# InWall_Schem2.net
KiCad netlist of a schematic drawn in Altium Designer
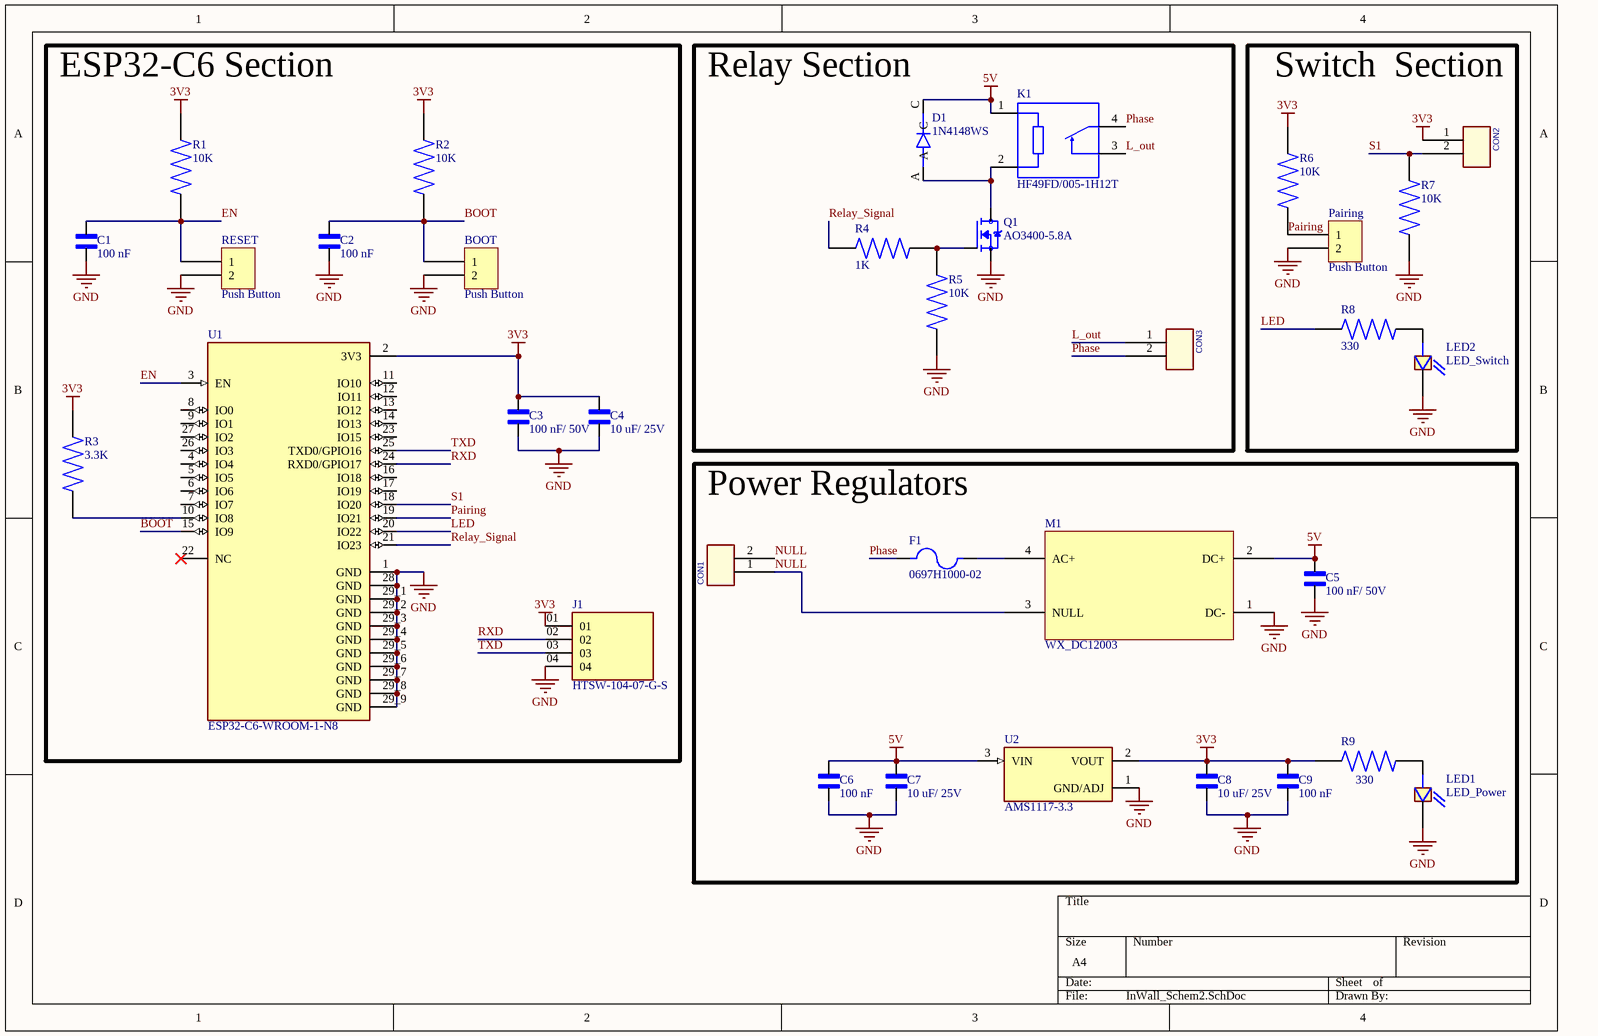
[diagram p0: InWall_Schem2.SchDoc]

(export (version "E")
  (design (tool "Eeschema 10.0.6"))
  (components
    (comp (ref "BOOT")
      (value "Push Button")
      (footprint "Push Button")
      (libsource (lib "zigbee_orangepi") (part "Push Button"))
    )
    (comp (ref "C1")
      (value "100 nF")
      (footprint "CAPC2012X90N")
      (description "Capacitor: ceramic; MLCC; 100nF; 25V; X7R; Â±10%; SMD; 0805")
      (fields (field (name "MF") "Vishay Vitramon") (field (name "MP") "VJ0805Y104KXXCW1BC"))
      (libsource (lib "Smart_InWall") (part "VJ0805Y104KXXCW1BC"))
    )
    (comp (ref "C2")
      (value "100 nF")
      (footprint "CAPC2012X90N")
      (description "Capacitor: ceramic; MLCC; 100nF; 25V; X7R; Â±10%; SMD; 0805")
      (fields (field (name "MF") "Vishay Vitramon") (field (name "MP") "VJ0805Y104KXXCW1BC"))
      (libsource (lib "Smart_InWall") (part "VJ0805Y104KXXCW1BC"))
    )
    (comp (ref "C3")
      (value "100 nF/ 50V")
      (footprint "CAPC2012X90N")
      (description "Capacitor: ceramic; MLCC; 100nF; 25V; X7R; Â±10%; SMD; 0805")
      (fields (field (name "MF") "Vishay Vitramon") (field (name "MP") "VJ0805Y104KXXCW1BC"))
      (libsource (lib "Smart_InWall") (part "VJ0805Y104KXXCW1BC"))
    )
    (comp (ref "C4")
      (value "10 uF/ 25V")
      (footprint "CAPC2012X90N")
      (description "Capacitor: ceramic; MLCC; 100nF; 25V; X7R; Â±10%; SMD; 0805")
      (fields (field (name "MF") "Vishay Vitramon") (field (name "MP") "VJ0805Y104KXXCW1BC"))
      (libsource (lib "Smart_InWall") (part "VJ0805Y104KXXCW1BC"))
    )
    (comp (ref "C5")
      (value "100 nF/ 50V")
      (footprint "CAPC2012X90N")
      (description "Capacitor: ceramic; MLCC; 100nF; 25V; X7R; Â±10%; SMD; 0805")
      (fields (field (name "MF") "Vishay Vitramon") (field (name "MP") "VJ0805Y104KXXCW1BC"))
      (libsource (lib "Smart_InWall") (part "VJ0805Y104KXXCW1BC"))
    )
    (comp (ref "C6")
      (value "100 nF")
      (footprint "CAPC2012X90N")
      (description "Capacitor: ceramic; MLCC; 100nF; 25V; X7R; Â±10%; SMD; 0805")
      (fields (field (name "MF") "Vishay Vitramon") (field (name "MP") "VJ0805Y104KXXCW1BC"))
      (libsource (lib "Smart_InWall") (part "VJ0805Y104KXXCW1BC"))
    )
    (comp (ref "C7")
      (value "10 uF/ 25V")
      (footprint "CAPC2012X90N")
      (description "Capacitor: ceramic; MLCC; 100nF; 25V; X7R; Â±10%; SMD; 0805")
      (fields (field (name "MF") "Vishay Vitramon") (field (name "MP") "VJ0805Y104KXXCW1BC"))
      (libsource (lib "Smart_InWall") (part "VJ0805Y104KXXCW1BC"))
    )
    (comp (ref "C8")
      (value "10 uF/ 25V")
      (footprint "CAPC2012X90N")
      (description "Capacitor: ceramic; MLCC; 100nF; 25V; X7R; Â±10%; SMD; 0805")
      (fields (field (name "MF") "Vishay Vitramon") (field (name "MP") "VJ0805Y104KXXCW1BC"))
      (libsource (lib "Smart_InWall") (part "VJ0805Y104KXXCW1BC"))
    )
    (comp (ref "C9")
      (value "100 nF")
      (footprint "CAPC2012X90N")
      (description "Capacitor: ceramic; MLCC; 100nF; 25V; X7R; Â±10%; SMD; 0805")
      (fields (field (name "MF") "Vishay Vitramon") (field (name "MP") "VJ0805Y104KXXCW1BC"))
      (libsource (lib "Smart_InWall") (part "VJ0805Y104KXXCW1BC"))
    )
    (comp (ref "CON1") (value "CON2") (footprint "TB_2") (libsource (lib "") (part "CON2_1")))
    (comp (ref "CON2") (value "CON2") (footprint "TB_2") (libsource (lib "Smart_InWall") (part "CON2")))
    (comp (ref "CON3") (value "CON2") (footprint "TB_2") (libsource (lib "Smart_InWall") (part "CON2")))
    (comp (ref "D1")
      (value "1N4148WS")
      (footprint "SODFL2512X100N")
      (description "Diode Standard 75V 300mA (DC) Surface Mount SOD-323")
      (fields (field (name "MF") "ON Semiconductor"))
      (libsource (lib "smartplug") (part "1N4148WS"))
    )
    (comp (ref "F1")
      (value "0697H1000-02")
      (footprint "FUSRR508W60L835T400H810")
      (description "2-Pin Radial Fuse ¦ Rectangular ¦ Slow Blow ¦ UL ¦ Ammo Pack ¦ 1A")
      (fields (field (name "MF") "Bel Fuse"))
      (libsource (lib "Smart_InWall") (part "0697H1000-02"))
    )
    (comp (ref "J1")
      (value "HTSW-104-07-G-S")
      (footprint "SAMTEC_HTSW-104-07-G-S")
      (libsource (lib "ZigbeeHub") (part "HTSW-104-07-G-S"))
    )
    (comp (ref "K1")
      (value "HF49FD/005-1H12T")
      (footprint "RELAY_HF49FD/005-1H12T")
      (description "Relay: electromagnetic; SPST-NO; Ucoil: 5VDC; 5A/250VAC; 5A/30VDC")
      (fields (field (name "MF") "Hongfa"))
      (libsource (lib "Smart_InWall") (part "HF49FD/005-1H12T"))
    )
    (comp (ref "LED1")
      (value "LED_Power")
      (footprint "LEDRD254W50D305H520P")
      (description "Ovlaw4Cb7 White LED 3mm (T-1) Round Lens Through Hole Package ¦ Optek (TT Electronics) OVLAW4CB7")
      (fields (field (name "MF") "TT Electronics/Optek") (field (name "MP") "OVLAW4CB7"))
      (libsource (lib "ZigbeeHub") (part "OVLAW4CB7"))
    )
    (comp (ref "LED2")
      (value "LED_Switch")
      (footprint "LEDRD254W50D305H520P")
      (description "Ovlaw4Cb7 White LED 3mm (T-1) Round Lens Through Hole Package ¦ Optek (TT Electronics) OVLAW4CB7")
      (fields (field (name "MF") "TT Electronics/Optek") (field (name "MP") "OVLAW4CB7"))
      (libsource (lib "ZigbeeHub") (part "OVLAW4CB7"))
    )
    (comp (ref "M1")
      (value "WX_DC12003")
      (footprint "WX-DC12003")
      (libsource (lib "Smart_InWall") (part "WX_DC12003"))
    )
    (comp (ref "Pairing")
      (value "Push Button")
      (footprint "Push Button")
      (libsource (lib "zigbee_orangepi") (part "Push Button"))
    )
    (comp (ref "Q1")
      (value "AO3400-5.8A")
      (footprint "SOT95P260X140-3N")
      (fields (field (name "MF") "{'manufacturer': u'MDD'}"))
      (libsource (lib "Smart_InWall") (part "AO3400-5.8A"))
    )
    (comp (ref "R1")
      (value "10K")
      (footprint "RESC2012X65N")
      (description "RES SMD 5.11KOHM 0.1% 1/10W 0805")
      (fields (field (name "MF") "TE Connectivity") (field (name "MP") "RN73C2A5K11BTD"))
      (libsource (lib "Smart_InWall") (part "RN73C2A5K11BTD"))
    )
    (comp (ref "R2")
      (value "10K")
      (footprint "RESC2012X65N")
      (description "RES SMD 5.11KOHM 0.1% 1/10W 0805")
      (fields (field (name "MF") "TE Connectivity") (field (name "MP") "RN73C2A5K11BTD"))
      (libsource (lib "Smart_InWall") (part "RN73C2A5K11BTD"))
    )
    (comp (ref "R3")
      (value "3.3K")
      (footprint "RESC2012X65N")
      (description "RES SMD 5.11KOHM 0.1% 1/10W 0805")
      (fields (field (name "MF") "TE Connectivity") (field (name "MP") "RN73C2A5K11BTD"))
      (libsource (lib "Smart_InWall") (part "RN73C2A5K11BTD"))
    )
    (comp (ref "R4")
      (value "1K")
      (footprint "RESC2012X65N")
      (description "RES SMD 5.11KOHM 0.1% 1/10W 0805")
      (fields (field (name "MF") "TE Connectivity") (field (name "MP") "RN73C2A5K11BTD"))
      (libsource (lib "Smart_InWall") (part "RN73C2A5K11BTD"))
    )
    (comp (ref "R5")
      (value "10K")
      (footprint "RESC2012X65N")
      (description "RES SMD 5.11KOHM 0.1% 1/10W 0805")
      (fields (field (name "MF") "TE Connectivity") (field (name "MP") "RN73C2A5K11BTD"))
      (libsource (lib "Smart_InWall") (part "RN73C2A5K11BTD"))
    )
    (comp (ref "R6")
      (value "10K")
      (footprint "RESC2012X65N")
      (description "RES SMD 5.11KOHM 0.1% 1/10W 0805")
      (fields (field (name "MF") "TE Connectivity") (field (name "MP") "RN73C2A5K11BTD"))
      (libsource (lib "Smart_InWall") (part "RN73C2A5K11BTD"))
    )
    (comp (ref "R7")
      (value "10K")
      (footprint "RESC2012X65N")
      (description "RES SMD 5.11KOHM 0.1% 1/10W 0805")
      (fields (field (name "MF") "TE Connectivity") (field (name "MP") "RN73C2A5K11BTD"))
      (libsource (lib "Smart_InWall") (part "RN73C2A5K11BTD"))
    )
    (comp (ref "R8")
      (value "330")
      (footprint "RESC2012X65N")
      (description "RES SMD 5.11KOHM 0.1% 1/10W 0805")
      (fields (field (name "MF") "TE Connectivity") (field (name "MP") "RN73C2A5K11BTD"))
      (libsource (lib "Smart_InWall") (part "RN73C2A5K11BTD"))
    )
    (comp (ref "R9")
      (value "330")
      (footprint "RESC2012X65N")
      (description "RES SMD 5.11KOHM 0.1% 1/10W 0805")
      (fields (field (name "MF") "TE Connectivity") (field (name "MP") "RN73C2A5K11BTD"))
      (libsource (lib "Smart_InWall") (part "RN73C2A5K11BTD"))
    )
    (comp (ref "RESET")
      (value "Push Button")
      (footprint "Push Button")
      (libsource (lib "zigbee_orangepi") (part "Push Button"))
    )
    (comp (ref "U1")
      (value "ESP32-C6-WROOM-1-N8")
      (footprint "XCVR_ESP32-C6-WROOM-1-N8")
      (fields (field (name "MF") "Espressif Systems"))
      (libsource (lib "Smart_InWall") (part "ESP32-C6-WROOM-1-N8"))
    )
    (comp (ref "U2")
      (value "AMS1117-3.3")
      (footprint "SOT229P700X180-4N")
      (description "Sot223/Pkg 1-Amp 3.3-Volt Low Drop Out Voltage Regulatator")
      (fields (field (name "MF") "Advanced Monolithic Systems"))
      (libsource (lib "ZigbeeHub") (part "AMS1117-3.3"))
    )
  )
  (nets
    (net (code "1") (name "/BOOT") (class "Default")
      (node (ref "BOOT") (pin "1") (pinfunction "1_1") (pintype "passive"))
      (node (ref "C2") (pin "2") (pinfunction "2_2") (pintype "passive"))
      (node (ref "R2") (pin "2") (pinfunction "2_2") (pintype "passive"))
      (node (ref "U1") (pin "15") (pinfunction "IO9_15") (pintype "bidirectional"))
    )
    (net (code "2") (name "/EN") (class "Default")
      (node (ref "C1") (pin "2") (pinfunction "2_2") (pintype "passive"))
      (node (ref "R1") (pin "2") (pinfunction "2_2") (pintype "passive"))
      (node (ref "RESET") (pin "1") (pinfunction "1_1") (pintype "passive"))
      (node (ref "U1") (pin "3") (pinfunction "EN_3") (pintype "input"))
    )
    (net (code "3") (name "/LED") (class "Default")
      (node (ref "R8") (pin "1") (pinfunction "1_1") (pintype "passive"))
      (node (ref "U1") (pin "20") (pinfunction "IO22_20") (pintype "bidirectional"))
    )
    (net (code "4") (name "/L_out") (class "Default")
      (node (ref "CON3") (pin "1") (pinfunction "1_1") (pintype "passive"))
      (node (ref "K1") (pin "3") (pinfunction "C2_3") (pintype "passive"))
    )
    (net (code "5") (name "/NULL") (class "Default")
      (node (ref "CON1") (pin "1") (pinfunction "1_1") (pintype "passive"))
      (node (ref "CON1") (pin "2") (pinfunction "2_2") (pintype "passive"))
      (node (ref "M1") (pin "3") (pinfunction "NULL_3") (pintype "passive"))
    )
    (net (code "6") (name "/Pairing") (class "Default")
      (node (ref "Pairing") (pin "1") (pinfunction "1_1") (pintype "passive"))
      (node (ref "R6") (pin "2") (pinfunction "2_2") (pintype "passive"))
      (node (ref "U1") (pin "19") (pinfunction "IO21_19") (pintype "bidirectional"))
    )
    (net (code "7") (name "/Phase") (class "Default")
      (node (ref "CON3") (pin "2") (pinfunction "2_2") (pintype "passive"))
      (node (ref "F1") (pin "1") (pinfunction "1_1") (pintype "passive"))
      (node (ref "K1") (pin "4") (pinfunction "C1_4") (pintype "passive"))
    )
    (net (code "8") (name "/RXD") (class "Default")
      (node (ref "J1") (pin "02") (pinfunction "02_02") (pintype "passive"))
      (node (ref "U1") (pin "24") (pinfunction "RXD0/GPIO17_24") (pintype "bidirectional"))
    )
    (net (code "9") (name "/Relay_Signal") (class "Default")
      (node (ref "R4") (pin "1") (pinfunction "1_1") (pintype "passive"))
      (node (ref "U1") (pin "21") (pinfunction "IO23_21") (pintype "bidirectional"))
    )
    (net (code "10") (name "/S1") (class "Default")
      (node (ref "CON2") (pin "2") (pinfunction "2_2") (pintype "passive"))
      (node (ref "R7") (pin "1") (pinfunction "1_1") (pintype "passive"))
      (node (ref "U1") (pin "18") (pinfunction "IO20_18") (pintype "bidirectional"))
    )
    (net (code "11") (name "/TXD") (class "Default")
      (node (ref "J1") (pin "03") (pinfunction "03_03") (pintype "passive"))
      (node (ref "U1") (pin "25") (pinfunction "TXD0/GPIO16_25") (pintype "bidirectional"))
    )
    (net (code "12") (name "3V3") (class "Default")
      (node (ref "C3") (pin "2") (pinfunction "2_2") (pintype "passive"))
      (node (ref "C4") (pin "2") (pinfunction "2_2") (pintype "passive"))
      (node (ref "C8") (pin "2") (pinfunction "2_2") (pintype "passive"))
      (node (ref "C9") (pin "2") (pinfunction "2_2") (pintype "passive"))
      (node (ref "CON2") (pin "1") (pinfunction "1_1") (pintype "passive"))
      (node (ref "J1") (pin "01") (pinfunction "01_01") (pintype "passive"))
      (node (ref "R1") (pin "1") (pinfunction "1_1") (pintype "passive"))
      (node (ref "R2") (pin "1") (pinfunction "1_1") (pintype "passive"))
      (node (ref "R3") (pin "2") (pinfunction "2_2") (pintype "passive"))
      (node (ref "R6") (pin "1") (pinfunction "1_1") (pintype "passive"))
      (node (ref "R9") (pin "1") (pinfunction "1_1") (pintype "passive"))
      (node (ref "U1") (pin "2") (pinfunction "3V3_2") (pintype "power_in"))
      (node (ref "U2") (pin "2") (pinfunction "VOUT_2") (pintype "power_in"))
    )
    (net (code "13") (name "5V") (class "Default")
      (node (ref "C5") (pin "2") (pinfunction "2_2") (pintype "passive"))
      (node (ref "C6") (pin "2") (pinfunction "2_2") (pintype "passive"))
      (node (ref "C7") (pin "2") (pinfunction "2_2") (pintype "passive"))
      (node (ref "D1") (pin "C") (pinfunction "C_C") (pintype "passive"))
      (node (ref "K1") (pin "1") (pinfunction "L1_1") (pintype "passive"))
      (node (ref "M1") (pin "2") (pinfunction "DC+_2") (pintype "passive"))
      (node (ref "U2") (pin "3") (pinfunction "VIN_3") (pintype "input"))
    )
    (net (code "14") (name "GND") (class "Default")
      (node (ref "BOOT") (pin "2") (pinfunction "2_2") (pintype "passive"))
      (node (ref "C1") (pin "1") (pinfunction "1_1") (pintype "passive"))
      (node (ref "C2") (pin "1") (pinfunction "1_1") (pintype "passive"))
      (node (ref "C3") (pin "1") (pinfunction "1_1") (pintype "passive"))
      (node (ref "C4") (pin "1") (pinfunction "1_1") (pintype "passive"))
      (node (ref "C5") (pin "1") (pinfunction "1_1") (pintype "passive"))
      (node (ref "C6") (pin "1") (pinfunction "1_1") (pintype "passive"))
      (node (ref "C7") (pin "1") (pinfunction "1_1") (pintype "passive"))
      (node (ref "C8") (pin "1") (pinfunction "1_1") (pintype "passive"))
      (node (ref "C9") (pin "1") (pinfunction "1_1") (pintype "passive"))
      (node (ref "J1") (pin "04") (pinfunction "04_04") (pintype "passive"))
      (node (ref "LED1") (pin "C") (pinfunction "C_C") (pintype "passive"))
      (node (ref "LED2") (pin "C") (pinfunction "C_C") (pintype "passive"))
      (node (ref "M1") (pin "1") (pinfunction "DC-_1") (pintype "passive"))
      (node (ref "Pairing") (pin "2") (pinfunction "2_2") (pintype "passive"))
      (node (ref "Q1") (pin "2") (pinfunction "S_2") (pintype "passive"))
      (node (ref "R5") (pin "1") (pinfunction "1_1") (pintype "passive"))
      (node (ref "R7") (pin "2") (pinfunction "2_2") (pintype "passive"))
      (node (ref "RESET") (pin "2") (pinfunction "2_2") (pintype "passive"))
      (node (ref "U1") (pin "1") (pinfunction "GND_1") (pintype "power_in"))
      (node (ref "U1") (pin "28") (pinfunction "GND_28") (pintype "power_in"))
      (node (ref "U1") (pin "29_1") (pinfunction "GND_29_1") (pintype "power_in"))
      (node (ref "U1") (pin "29_2") (pinfunction "GND_29_2") (pintype "power_in"))
      (node (ref "U1") (pin "29_3") (pinfunction "GND_29_3") (pintype "power_in"))
      (node (ref "U1") (pin "29_4") (pinfunction "GND_29_4") (pintype "power_in"))
      (node (ref "U1") (pin "29_5") (pinfunction "GND_29_5") (pintype "power_in"))
      (node (ref "U1") (pin "29_6") (pinfunction "GND_29_6") (pintype "power_in"))
      (node (ref "U1") (pin "29_7") (pinfunction "GND_29_7") (pintype "power_in"))
      (node (ref "U1") (pin "29_8") (pinfunction "GND_29_8") (pintype "power_in"))
      (node (ref "U1") (pin "29_9") (pinfunction "GND_29_9") (pintype "power_in"))
      (node (ref "U2") (pin "1") (pinfunction "GND/ADJ_1") (pintype "power_in"))
    )
    (net (code "15") (name "Net-(K1-L2)") (class "Default")
      (node (ref "D1") (pin "A") (pinfunction "A_A") (pintype "passive"))
      (node (ref "K1") (pin "2") (pinfunction "L2_2") (pintype "passive"))
      (node (ref "Q1") (pin "3") (pinfunction "D_3") (pintype "passive"))
    )
    (net (code "16") (name "Net-(LED1-PadA)") (class "Default")
      (node (ref "LED1") (pin "A") (pinfunction "A_A") (pintype "passive"))
      (node (ref "R9") (pin "2") (pinfunction "2_2") (pintype "passive"))
    )
    (net (code "17") (name "Net-(LED2-PadA)") (class "Default")
      (node (ref "LED2") (pin "A") (pinfunction "A_A") (pintype "passive"))
      (node (ref "R8") (pin "2") (pinfunction "2_2") (pintype "passive"))
    )
    (net (code "18") (name "Net-(M1-AC+)") (class "Default")
      (node (ref "F1") (pin "2") (pinfunction "2_2") (pintype "passive"))
      (node (ref "M1") (pin "4") (pinfunction "AC+_4") (pintype "passive"))
    )
    (net (code "19") (name "Net-(Q1-G)") (class "Default")
      (node (ref "Q1") (pin "1") (pinfunction "G_1") (pintype "passive"))
      (node (ref "R4") (pin "2") (pinfunction "2_2") (pintype "passive"))
      (node (ref "R5") (pin "2") (pinfunction "2_2") (pintype "passive"))
    )
    (net (code "20") (name "Net-(U1-IO8)") (class "Default")
      (node (ref "R3") (pin "1") (pinfunction "1_1") (pintype "passive"))
      (node (ref "U1") (pin "10") (pinfunction "IO8_10") (pintype "bidirectional"))
    )
    (net (code "21") (name "unconnected-(U1-IO0-Pad8)") (class "Default")
      (node (ref "U1") (pin "8") (pinfunction "IO0_8") (pintype "bidirectional"))
    )
    (net (code "22") (name "unconnected-(U1-IO1-Pad9)") (class "Default")
      (node (ref "U1") (pin "9") (pinfunction "IO1_9") (pintype "bidirectional"))
    )
    (net (code "23") (name "unconnected-(U1-IO2-Pad27)") (class "Default")
      (node (ref "U1") (pin "27") (pinfunction "IO2_27") (pintype "bidirectional"))
    )
    (net (code "24") (name "unconnected-(U1-IO3-Pad26)") (class "Default")
      (node (ref "U1") (pin "26") (pinfunction "IO3_26") (pintype "bidirectional"))
    )
    (net (code "25") (name "unconnected-(U1-IO4-Pad4)") (class "Default")
      (node (ref "U1") (pin "4") (pinfunction "IO4_4") (pintype "bidirectional"))
    )
    (net (code "26") (name "unconnected-(U1-IO5-Pad5)") (class "Default")
      (node (ref "U1") (pin "5") (pinfunction "IO5_5") (pintype "bidirectional"))
    )
    (net (code "27") (name "unconnected-(U1-IO6-Pad6)") (class "Default")
      (node (ref "U1") (pin "6") (pinfunction "IO6_6") (pintype "bidirectional"))
    )
    (net (code "28") (name "unconnected-(U1-IO7-Pad7)") (class "Default")
      (node (ref "U1") (pin "7") (pinfunction "IO7_7") (pintype "bidirectional"))
    )
    (net (code "29") (name "unconnected-(U1-IO10-Pad11)") (class "Default")
      (node (ref "U1") (pin "11") (pinfunction "IO10_11") (pintype "bidirectional"))
    )
    (net (code "30") (name "unconnected-(U1-IO11-Pad12)") (class "Default")
      (node (ref "U1") (pin "12") (pinfunction "IO11_12") (pintype "bidirectional"))
    )
    (net (code "31") (name "unconnected-(U1-IO12-Pad13)") (class "Default")
      (node (ref "U1") (pin "13") (pinfunction "IO12_13") (pintype "bidirectional"))
    )
    (net (code "32") (name "unconnected-(U1-IO13-Pad14)") (class "Default")
      (node (ref "U1") (pin "14") (pinfunction "IO13_14") (pintype "bidirectional"))
    )
    (net (code "33") (name "unconnected-(U1-IO15-Pad23)") (class "Default")
      (node (ref "U1") (pin "23") (pinfunction "IO15_23") (pintype "bidirectional"))
    )
    (net (code "34") (name "unconnected-(U1-IO18-Pad16)") (class "Default")
      (node (ref "U1") (pin "16") (pinfunction "IO18_16") (pintype "bidirectional"))
    )
    (net (code "35") (name "unconnected-(U1-IO19-Pad17)") (class "Default")
      (node (ref "U1") (pin "17") (pinfunction "IO19_17") (pintype "bidirectional"))
    )
    (net (code "36") (name "unconnected-(U1-NC-Pad22)") (class "Default")
      (node (ref "U1") (pin "22") (pinfunction "NC_22") (pintype "passive+no_connect"))
    )
  )
)
